# e-paper_ESP32-Pico-D4.net
KiCad netlist of a schematic drawn in EasyEDA Pro
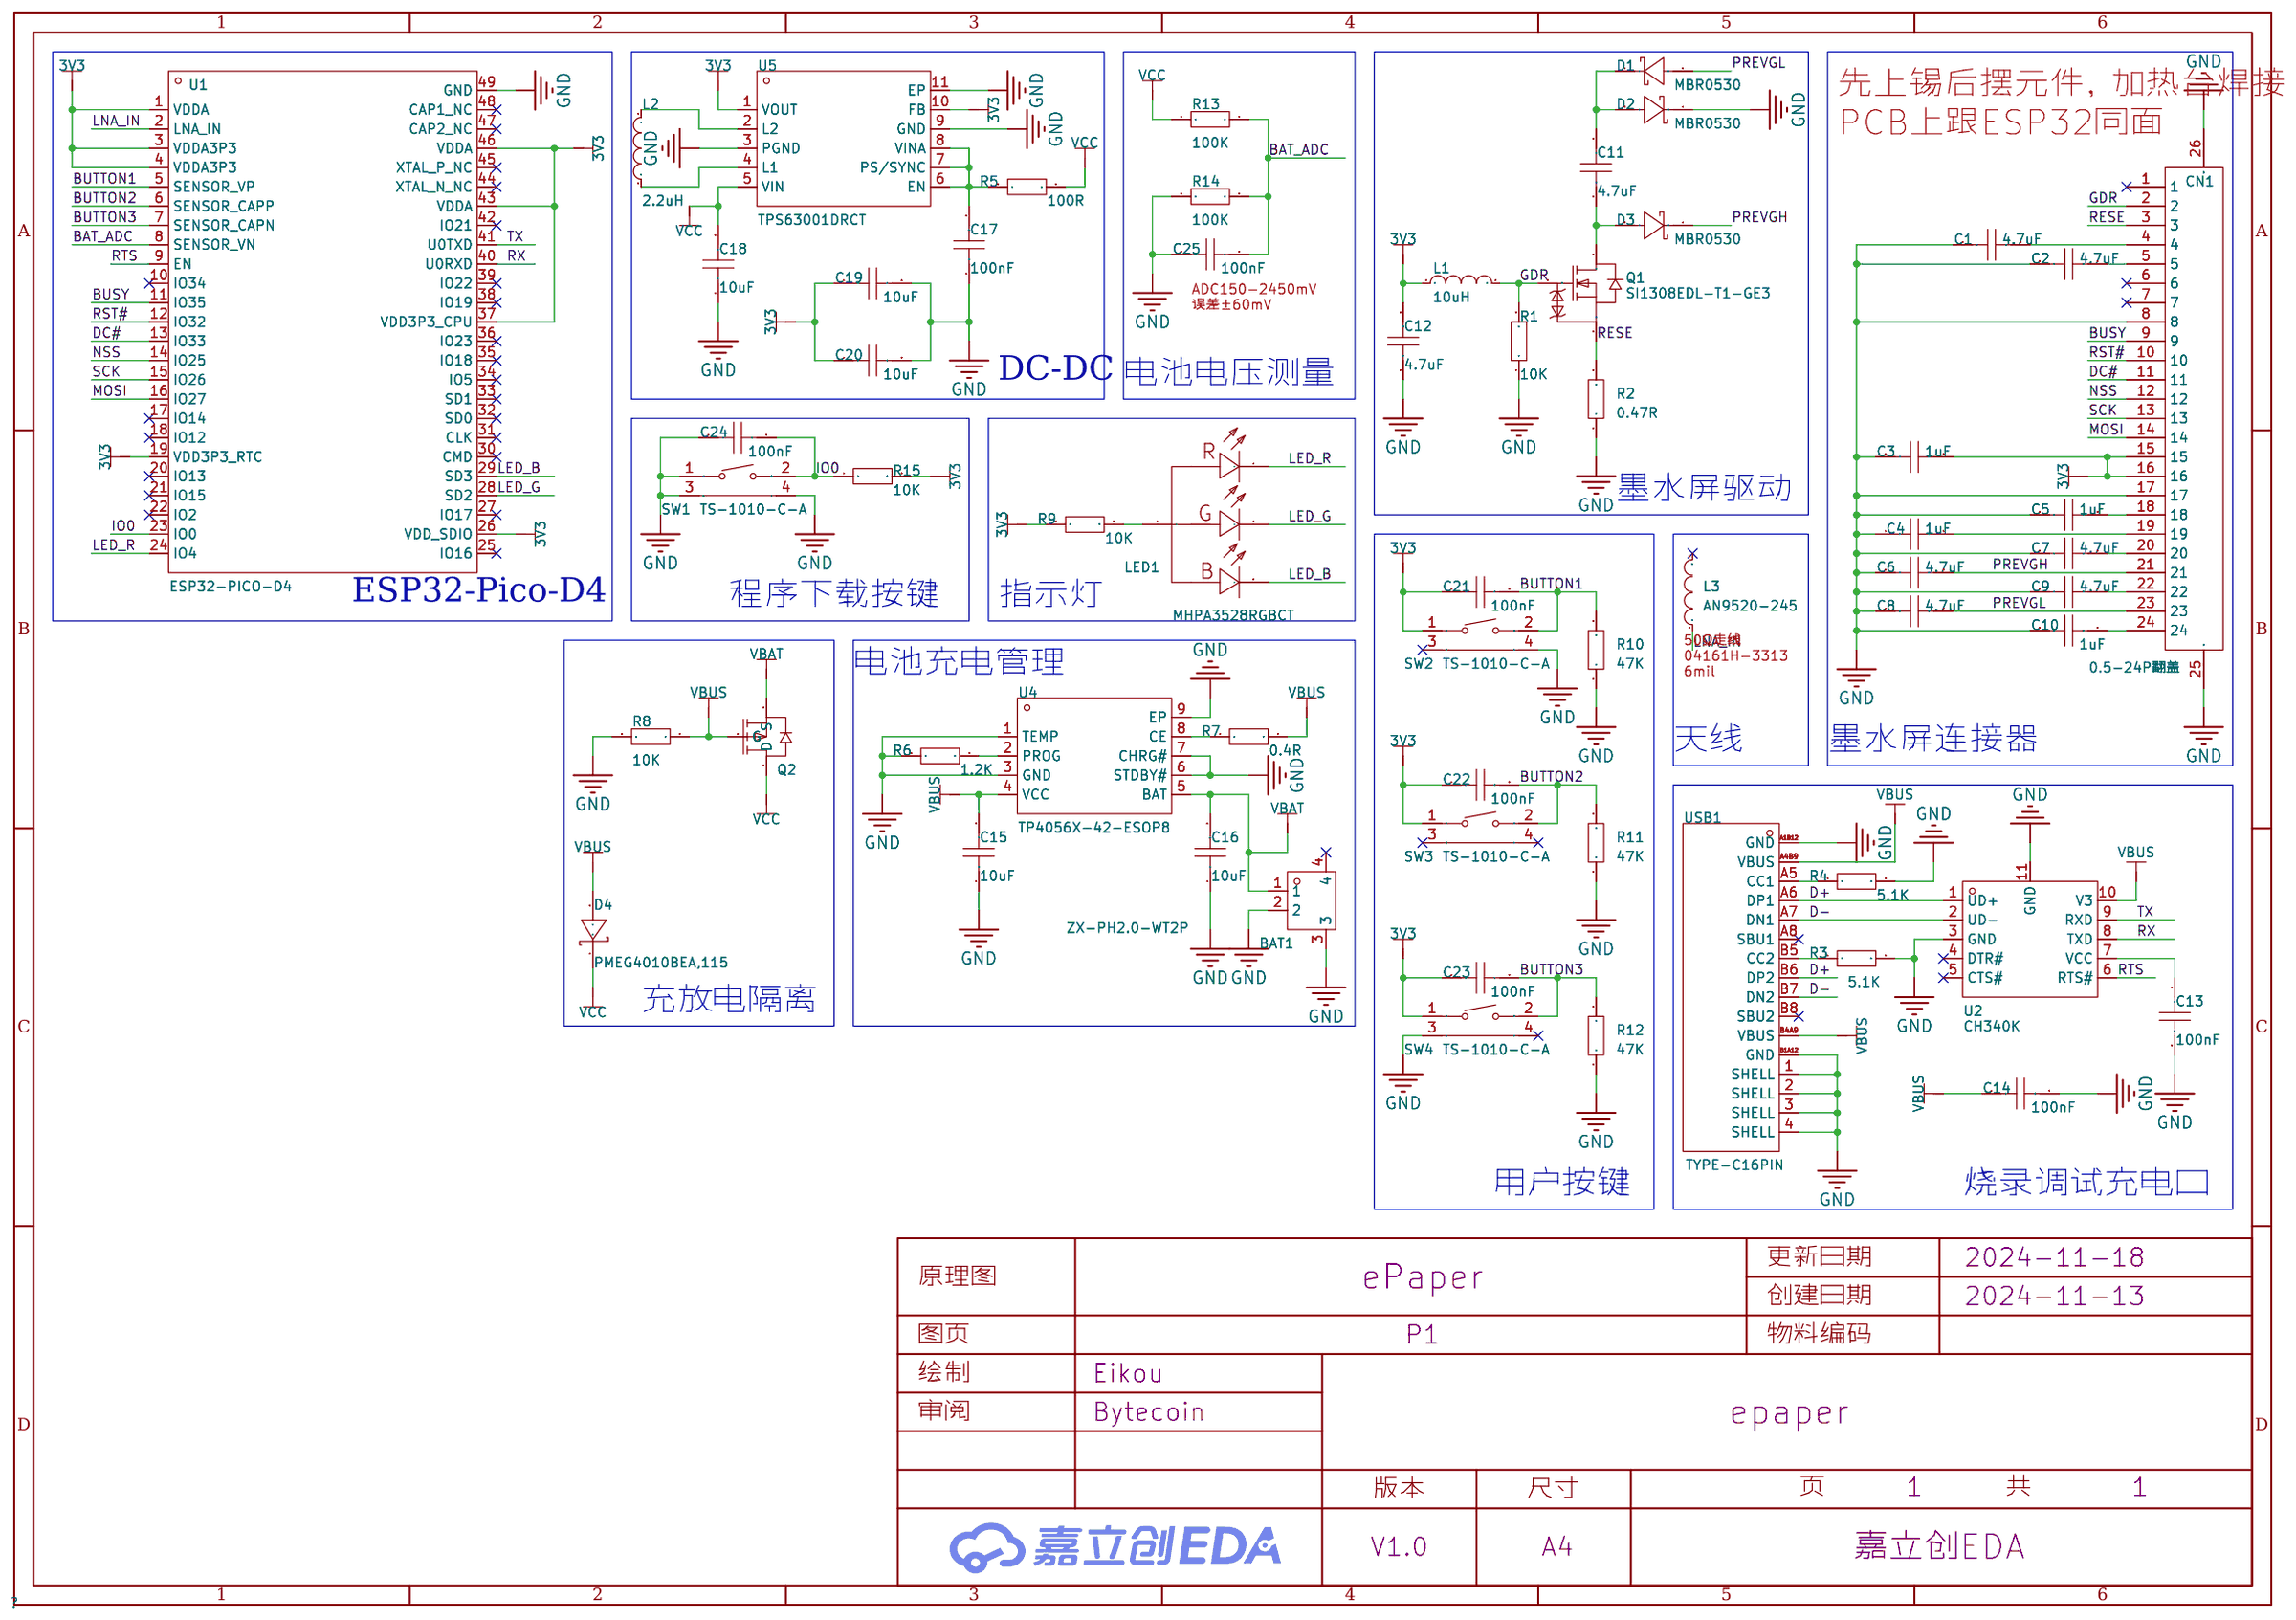
[diagram p0: schematic sheet]

(export (version "E")
  (design (tool "Eeschema 10.0.6"))
  (components
    (comp (ref "BAT1")
      (value "ZX-PH2.0-WT2P")
      (footprint "easyedapro:CONN-SMD_ZX-PH2.0-WT2P")
      (fields (field (name "Manufacturer") "Megastar(兆星)"))
      (libsource (lib "easyedapro") (part "ZX-PH2.0-WT2P"))
    )
    (comp (ref "C1")
      (value "4.7uF")
      (footprint "easyedapro:C0603")
      (libsource (lib "easyedapro") (part "CapAcitance"))
    )
    (comp (ref "C2")
      (value "4.7uF")
      (footprint "easyedapro:C0603")
      (libsource (lib "easyedapro") (part "CapAcitance"))
    )
    (comp (ref "C3")
      (value "1uF")
      (footprint "easyedapro:C0603")
      (libsource (lib "easyedapro") (part "CapAcitance"))
    )
    (comp (ref "C4")
      (value "1uF")
      (footprint "easyedapro:C0603")
      (libsource (lib "easyedapro") (part "CapAcitance"))
    )
    (comp (ref "C5")
      (value "1uF")
      (footprint "easyedapro:C0603")
      (libsource (lib "easyedapro") (part "CapAcitance"))
    )
    (comp (ref "C6")
      (value "4.7uF")
      (footprint "easyedapro:C0603")
      (libsource (lib "easyedapro") (part "CapAcitance"))
    )
    (comp (ref "C7")
      (value "4.7uF")
      (footprint "easyedapro:C0603")
      (libsource (lib "easyedapro") (part "CapAcitance"))
    )
    (comp (ref "C8")
      (value "4.7uF")
      (footprint "easyedapro:C0603")
      (libsource (lib "easyedapro") (part "CapAcitance"))
    )
    (comp (ref "C9")
      (value "4.7uF")
      (footprint "easyedapro:C0603")
      (libsource (lib "easyedapro") (part "CapAcitance"))
    )
    (comp (ref "C10")
      (value "1uF")
      (footprint "easyedapro:C0603")
      (libsource (lib "easyedapro") (part "CapAcitance"))
    )
    (comp (ref "C11")
      (value "4.7uF")
      (footprint "easyedapro:C0603")
      (libsource (lib "easyedapro") (part "CapAcitance"))
    )
    (comp (ref "C12")
      (value "4.7uF")
      (footprint "easyedapro:C0603")
      (libsource (lib "easyedapro") (part "CapAcitance"))
    )
    (comp (ref "C13")
      (value "100nF")
      (footprint "easyedapro:C0603")
      (libsource (lib "easyedapro") (part "CapAcitance"))
    )
    (comp (ref "C14")
      (value "100nF")
      (footprint "easyedapro:C0603")
      (libsource (lib "easyedapro") (part "CapAcitance"))
    )
    (comp (ref "C15")
      (value "10uF")
      (footprint "easyedapro:C0603")
      (libsource (lib "easyedapro") (part "CapAcitance"))
    )
    (comp (ref "C16")
      (value "10uF")
      (footprint "easyedapro:C0603")
      (libsource (lib "easyedapro") (part "CapAcitance"))
    )
    (comp (ref "C17")
      (value "100nF")
      (footprint "easyedapro:C0603")
      (libsource (lib "easyedapro") (part "CapAcitance"))
    )
    (comp (ref "C18")
      (value "10uF")
      (footprint "easyedapro:C0603")
      (libsource (lib "easyedapro") (part "CapAcitance"))
    )
    (comp (ref "C19")
      (value "10uF")
      (footprint "easyedapro:C0603")
      (libsource (lib "easyedapro") (part "CapAcitance"))
    )
    (comp (ref "C20")
      (value "10uF")
      (footprint "easyedapro:C0603")
      (libsource (lib "easyedapro") (part "CapAcitance"))
    )
    (comp (ref "C21")
      (value "100nF")
      (footprint "easyedapro:C0603")
      (libsource (lib "easyedapro") (part "CapAcitance"))
    )
    (comp (ref "C22")
      (value "100nF")
      (footprint "easyedapro:C0603")
      (libsource (lib "easyedapro") (part "CapAcitance"))
    )
    (comp (ref "C23")
      (value "100nF")
      (footprint "easyedapro:C0603")
      (libsource (lib "easyedapro") (part "CapAcitance"))
    )
    (comp (ref "C24")
      (value "100nF")
      (footprint "easyedapro:C0603")
      (libsource (lib "easyedapro") (part "CapAcitance"))
    )
    (comp (ref "C25")
      (value "100nF")
      (footprint "easyedapro:C0603")
      (libsource (lib "easyedapro") (part "CapAcitance"))
    )
    (comp (ref "CN1")
      (value "0.5-24P翻盖")
      (footprint "easyedapro:FPC-SMD_24P-P0.50-L6.1-W16.4")
      (description "间距:0.5mm;触点数量:24P;锁定特性:翻盖式;触点类型:下接;安装类型:卧贴;工作温度范围:-;")
      (fields (field (name "Manufacturer") "BOOMELE(博穆精密)"))
      (libsource (lib "easyedapro") (part "FPC-Pitch0.5-24P-Bottom-Contact-Flip-Lock"))
    )
    (comp (ref "D1")
      (value "MBR0530")
      (footprint "easyedapro:SOD-123_L2.7-W1.6-LS3.7-RD-1")
      (description "二极管配置:独立式;正向压降(Vf):500mV@500mA;直流反向耐压(Vr):30V;整流电流:500mA;")
      (fields (field (name "Manufacturer") "TWGMC(台湾迪嘉)"))
      (libsource (lib "easyedapro") (part "MBR0530_C5204746"))
    )
    (comp (ref "D2")
      (value "MBR0530")
      (footprint "easyedapro:SOD-123_L2.7-W1.6-LS3.7-RD-1")
      (description "二极管配置:独立式;正向压降(Vf):500mV@500mA;直流反向耐压(Vr):30V;整流电流:500mA;")
      (fields (field (name "Manufacturer") "TWGMC(台湾迪嘉)"))
      (libsource (lib "easyedapro") (part "MBR0530_C5204746"))
    )
    (comp (ref "D3")
      (value "MBR0530")
      (footprint "easyedapro:SOD-123_L2.7-W1.6-LS3.7-RD-1")
      (description "二极管配置:独立式;正向压降(Vf):500mV@500mA;直流反向耐压(Vr):30V;整流电流:500mA;")
      (fields (field (name "Manufacturer") "TWGMC(台湾迪嘉)"))
      (libsource (lib "easyedapro") (part "MBR0530_C5204746"))
    )
    (comp (ref "D4")
      (value "PMEG4010BEA,115")
      (fields (field (name "Manufacturer") "Nexperia(安世)"))
      (libsource (lib "easyedapro") (part "SS16"))
    )
    (comp (ref "L1")
      (value "10uH")
      (footprint "easyedapro:IND-SMD_L4.6-W4.1")
      (description "电感值:6.8uH;精度:±20%;额定电流:2A;饱和电流(Isat):2.5A;类型:一体成型电感;")
      (fields (field (name "Manufacturer Part") "CKST0402-10uH/M") (field (name "Manufacturer") "CENKER(岑科)"))
      (libsource (lib "easyedapro") (part "CKST0402-6.8UH/M"))
    )
    (comp (ref "L2")
      (value "2.2uH")
      (footprint "easyedapro:IND-SMD_L4.6-W4.1")
      (description "电感值:6.8uH;精度:±20%;额定电流:2A;饱和电流(Isat):2.5A;类型:一体成型电感;")
      (fields
        (field (name "Manufacturer Part") "CKST0402-2.2uH/M")
        (field (name "Manufacturer") "CENKER(岑科)")
      )
      (libsource (lib "easyedapro") (part "CKST0402-6.8UH/M"))
    )
    (comp (ref "L3")
      (value "AN9520-245")
      (footprint "easyedapro:ANT-SMD_L9.5-W2.1")
      (description "2.4G陶瓷天线/适用于WIFI蓝牙")
      (fields (field (name "Manufacturer") "rainsun(霖昱微)"))
      (libsource (lib "easyedapro") (part "AN9520-245"))
    )
    (comp (ref "LED1")
      (value "MHPA3528RGBCT")
      (footprint "easyedapro:LED-ARRAY-SMD_4P-L3.5-W2.8-TL")
      (fields (field (name "Manufacturer") "MEIHUA(美华)"))
      (libsource (lib "easyedapro") (part "MHPA3528RGBCT"))
    )
    (comp (ref "Q1")
      (value "SI1308EDL-T1-GE3")
      (footprint "easyedapro:SOT-323_L2.0-W1.3-P1.30-LS2.1-BR")
      (description "类型:N沟道;漏源电压(Vdss):30V;连续漏极电流(Id):1.4A;功率(Pd):400mW；500mW;导通电阻(RDS(on)@Vgs,Id):132mΩ@10V,1.4A;")
      (fields (field (name "Manufacturer") "VISHAY(威世)"))
      (libsource (lib "easyedapro") (part "SI1308EDL-T1-GE3"))
    )
    (comp (ref "Q2")
      (value "~")
      (footprint "easyedapro:AO3401A_SOT-23-3")
      (libsource (lib "easyedapro") (part "P_MOS"))
    )
    (comp (ref "R1") (value "10K") (footprint "easyedapro:R0603") (libsource (lib "easyedapro") (part "电阻")))
    (comp (ref "R2")
      (value "0.47R")
      (footprint "easyedapro:R0603")
      (libsource (lib "easyedapro") (part "电阻"))
    )
    (comp (ref "R3") (value "5.1K") (footprint "easyedapro:R0603") (libsource (lib "easyedapro") (part "电阻")))
    (comp (ref "R4") (value "5.1K") (footprint "easyedapro:R0603") (libsource (lib "easyedapro") (part "电阻")))
    (comp (ref "R5") (value "100R") (footprint "easyedapro:R0603") (libsource (lib "easyedapro") (part "电阻")))
    (comp (ref "R6") (value "1.2K") (footprint "easyedapro:R0603") (libsource (lib "easyedapro") (part "电阻")))
    (comp (ref "R7") (value "0.4R") (footprint "easyedapro:R0603") (libsource (lib "easyedapro") (part "电阻")))
    (comp (ref "R8") (value "10K") (footprint "easyedapro:R0603") (libsource (lib "easyedapro") (part "电阻")))
    (comp (ref "R9") (value "10K") (footprint "easyedapro:R0603") (libsource (lib "easyedapro") (part "电阻")))
    (comp (ref "R10") (value "47K") (footprint "easyedapro:R0603") (libsource (lib "easyedapro") (part "电阻")))
    (comp (ref "R11") (value "47K") (footprint "easyedapro:R0603") (libsource (lib "easyedapro") (part "电阻")))
    (comp (ref "R12") (value "47K") (footprint "easyedapro:R0603") (libsource (lib "easyedapro") (part "电阻")))
    (comp (ref "R13")
      (value "100K")
      (footprint "easyedapro:R0603")
      (libsource (lib "easyedapro") (part "电阻"))
    )
    (comp (ref "R14")
      (value "100K")
      (footprint "easyedapro:R0603")
      (libsource (lib "easyedapro") (part "电阻"))
    )
    (comp (ref "R15") (value "10K") (footprint "easyedapro:R0603") (libsource (lib "easyedapro") (part "电阻")))
    (comp (ref "SW1")
      (value "TS-1010-C-A")
      (footprint "easyedapro:KEY-SMD_TX-1010-X-X")
      (fields (field (name "Manufacturer") "XKB Connectivity(中国星坤)"))
      (libsource (lib "easyedapro") (part "TS-1010-C-A"))
    )
    (comp (ref "SW2")
      (value "TS-1010-C-A")
      (footprint "easyedapro:KEY-SMD_TX-1010-X-X")
      (fields (field (name "Manufacturer") "XKB Connectivity(中国星坤)"))
      (libsource (lib "easyedapro") (part "TS-1010-C-A"))
    )
    (comp (ref "SW3")
      (value "TS-1010-C-A")
      (footprint "easyedapro:KEY-SMD_TX-1010-X-X")
      (fields (field (name "Manufacturer") "XKB Connectivity(中国星坤)"))
      (libsource (lib "easyedapro") (part "TS-1010-C-A"))
    )
    (comp (ref "SW4")
      (value "TS-1010-C-A")
      (footprint "easyedapro:KEY-SMD_TX-1010-X-X")
      (fields (field (name "Manufacturer") "XKB Connectivity(中国星坤)"))
      (libsource (lib "easyedapro") (part "TS-1010-C-A"))
    )
    (comp (ref "U1")
      (value "ESP32-PICO-D4")
      (footprint "easyedapro:LGA-48_L7.0-W7.0-P0.50-BL-EP5.4")
      (fields (field (name "Manufacturer") "ESPRESSIF(乐鑫)"))
      (libsource (lib "easyedapro") (part "ESP32-PICO-D4"))
    )
    (comp (ref "U2")
      (value "CH340K")
      (footprint "easyedapro:ESOP-10_L4.9-W3.9-P1.00-LS6.0-BL-EP")
      (description "应用功能:USB转串口;接口协议:USB 2.0;通道数:1;数据速率:2Mbps;")
      (fields (field (name "Manufacturer") "WCH(南京沁恒)"))
      (libsource (lib "easyedapro") (part "CH340K_C18208922"))
    )
    (comp (ref "U4")
      (value "TP4056X-42-ESOP8")
      (footprint "easyedapro:SOP-8_L4.9-W3.9-P1.27-LS6.0-TL-EP")
      (fields (field (name "Manufacturer") "TOPPOWER(南京拓微)"))
      (libsource (lib "easyedapro") (part "TP4056X_C2763448"))
    )
    (comp (ref "U5")
      (value "TPS63001DRCT")
      (footprint "easyedapro:VSON-10_L3.0-W3.0-P0.50-TL-EP")
      (description "功能类型:升降压型;输出类型:固定;输入电压:1.8V~5.5V;输出电压:3.3V;输出电流:1.6A;")
      (fields (field (name "Manufacturer") "TI(德州仪器)"))
      (libsource (lib "easyedapro") (part "TPS63001DRCT"))
    )
    (comp (ref "USB1")
      (value "TYPE-C16PIN")
      (footprint "easyedapro:USB-C-SMD_TYPE-C16PIN")
      (description "连接器类型:Type-C;标准:-;公母:母座;触点数量:16;端口数量:1;安装方式:卧贴;额定电流 - 电源:3A;工作温度范围:-40~+85;")
      (fields (field (name "Manufacturer") "SHOU HAN(首韩)"))
      (libsource (lib "easyedapro") (part "TYPE-C16PIN"))
    )
  )
  (nets
    (net (code "1") (name "/BAT_ADC") (class "Default")
      (node (ref "C25") (pin "2") (pinfunction "2_2") (pintype "input"))
      (node (ref "R13") (pin "1") (pinfunction "1_1") (pintype "input"))
      (node (ref "R14") (pin "1") (pinfunction "1_1") (pintype "input"))
      (node (ref "U1") (pin "8") (pinfunction "SENSOR_VN_8") (pintype "unspecified"))
    )
    (net (code "2") (name "/BUSY") (class "Default")
      (node (ref "CN1") (pin "9") (pinfunction "9_9") (pintype "unspecified"))
      (node (ref "U1") (pin "11") (pinfunction "IO35_11") (pintype "unspecified"))
    )
    (net (code "3") (name "/BUTTON1") (class "Default")
      (node (ref "C21") (pin "2") (pinfunction "2_2") (pintype "input"))
      (node (ref "R10") (pin "2") (pinfunction "2_2") (pintype "input"))
      (node (ref "SW2") (pin "2") (pinfunction "2_2") (pintype "unspecified"))
      (node (ref "U1") (pin "5") (pinfunction "SENSOR_VP_5") (pintype "unspecified"))
    )
    (net (code "4") (name "/BUTTON2") (class "Default")
      (node (ref "C22") (pin "2") (pinfunction "2_2") (pintype "input"))
      (node (ref "R11") (pin "2") (pinfunction "2_2") (pintype "input"))
      (node (ref "SW3") (pin "2") (pinfunction "2_2") (pintype "unspecified"))
      (node (ref "U1") (pin "6") (pinfunction "SENSOR_CAPP_6") (pintype "unspecified"))
    )
    (net (code "5") (name "/BUTTON3") (class "Default")
      (node (ref "C23") (pin "2") (pinfunction "2_2") (pintype "input"))
      (node (ref "R12") (pin "2") (pinfunction "2_2") (pintype "input"))
      (node (ref "SW4") (pin "2") (pinfunction "2_2") (pintype "unspecified"))
      (node (ref "U1") (pin "7") (pinfunction "SENSOR_CAPN_7") (pintype "unspecified"))
    )
    (net (code "6") (name "/D+") (class "Default")
      (node (ref "U2") (pin "1") (pinfunction "UD+_1") (pintype "unspecified"))
      (node (ref "USB1") (pin "A6") (pinfunction "DP1_A6") (pintype "input"))
      (node (ref "USB1") (pin "B6") (pinfunction "DP2_B6") (pintype "input"))
    )
    (net (code "7") (name "/D-") (class "Default")
      (node (ref "U2") (pin "2") (pinfunction "UD-_2") (pintype "unspecified"))
      (node (ref "USB1") (pin "A7") (pinfunction "DN1_A7") (pintype "input"))
      (node (ref "USB1") (pin "B7") (pinfunction "DN2_B7") (pintype "input"))
    )
    (net (code "8") (name "/DC#") (class "Default")
      (node (ref "CN1") (pin "11") (pinfunction "11_11") (pintype "unspecified"))
      (node (ref "U1") (pin "13") (pinfunction "IO33_13") (pintype "unspecified"))
    )
    (net (code "9") (name "/GDR") (class "Default")
      (node (ref "CN1") (pin "2") (pinfunction "2_2") (pintype "unspecified"))
      (node (ref "L1") (pin "2") (pinfunction "2_2") (pintype "unspecified"))
      (node (ref "Q1") (pin "1") (pinfunction "G_1") (pintype "input"))
      (node (ref "R1") (pin "2") (pinfunction "2_2") (pintype "input"))
    )
    (net (code "10") (name "/IO0") (class "Default")
      (node (ref "C24") (pin "2") (pinfunction "2_2") (pintype "input"))
      (node (ref "R15") (pin "1") (pinfunction "1_1") (pintype "input"))
      (node (ref "SW1") (pin "2") (pinfunction "2_2") (pintype "unspecified"))
      (node (ref "U1") (pin "23") (pinfunction "IO0_23") (pintype "unspecified"))
    )
    (net (code "11") (name "/LED_B") (class "Default")
      (node (ref "LED1") (pin "2") (pinfunction "-_2") (pintype "unspecified"))
      (node (ref "U1") (pin "29") (pinfunction "SD3_29") (pintype "unspecified"))
    )
    (net (code "12") (name "/LED_G") (class "Default")
      (node (ref "LED1") (pin "3") (pinfunction "-_3") (pintype "unspecified"))
      (node (ref "U1") (pin "28") (pinfunction "SD2_28") (pintype "unspecified"))
    )
    (net (code "13") (name "/LED_R") (class "Default")
      (node (ref "LED1") (pin "4") (pinfunction "-_4") (pintype "unspecified"))
      (node (ref "U1") (pin "24") (pinfunction "IO4_24") (pintype "unspecified"))
    )
    (net (code "14") (name "/LNA_IN") (class "Default")
      (node (ref "L3") (pin "1") (pinfunction "1_1") (pintype "unspecified"))
      (node (ref "U1") (pin "2") (pinfunction "LNA_IN_2") (pintype "unspecified"))
    )
    (net (code "15") (name "/MOSI") (class "Default")
      (node (ref "CN1") (pin "14") (pinfunction "14_14") (pintype "unspecified"))
      (node (ref "U1") (pin "16") (pinfunction "IO27_16") (pintype "unspecified"))
    )
    (net (code "16") (name "/NSS") (class "Default")
      (node (ref "CN1") (pin "12") (pinfunction "12_12") (pintype "unspecified"))
      (node (ref "U1") (pin "14") (pinfunction "IO25_14") (pintype "unspecified"))
    )
    (net (code "17") (name "/PREVGH") (class "Default")
      (node (ref "C6") (pin "2") (pinfunction "2_2") (pintype "input"))
      (node (ref "CN1") (pin "21") (pinfunction "21_21") (pintype "unspecified"))
      (node (ref "D3") (pin "1") (pinfunction "K_1") (pintype "unspecified"))
    )
    (net (code "18") (name "/PREVGL") (class "Default")
      (node (ref "C8") (pin "2") (pinfunction "2_2") (pintype "input"))
      (node (ref "CN1") (pin "23") (pinfunction "23_23") (pintype "unspecified"))
      (node (ref "D1") (pin "2") (pinfunction "A_2") (pintype "unspecified"))
    )
    (net (code "19") (name "/RESE") (class "Default")
      (node (ref "CN1") (pin "3") (pinfunction "3_3") (pintype "unspecified"))
      (node (ref "Q1") (pin "2") (pinfunction "S_2") (pintype "input"))
      (node (ref "R2") (pin "2") (pinfunction "2_2") (pintype "input"))
    )
    (net (code "20") (name "/RST#") (class "Default")
      (node (ref "CN1") (pin "10") (pinfunction "10_10") (pintype "unspecified"))
      (node (ref "U1") (pin "12") (pinfunction "IO32_12") (pintype "unspecified"))
    )
    (net (code "21") (name "/RTS") (class "Default")
      (node (ref "U1") (pin "9") (pinfunction "EN_9") (pintype "unspecified"))
      (node (ref "U2") (pin "6") (pinfunction "RTS#_6") (pintype "unspecified"))
    )
    (net (code "22") (name "/RX") (class "Default")
      (node (ref "U1") (pin "40") (pinfunction "U0RXD_40") (pintype "unspecified"))
      (node (ref "U2") (pin "8") (pinfunction "TXD_8") (pintype "unspecified"))
    )
    (net (code "23") (name "/SCK") (class "Default")
      (node (ref "CN1") (pin "13") (pinfunction "13_13") (pintype "unspecified"))
      (node (ref "U1") (pin "15") (pinfunction "IO26_15") (pintype "unspecified"))
    )
    (net (code "24") (name "/TX") (class "Default")
      (node (ref "U1") (pin "41") (pinfunction "U0TXD_41") (pintype "unspecified"))
      (node (ref "U2") (pin "9") (pinfunction "RXD_9") (pintype "unspecified"))
    )
    (net (code "25") (name "3V3") (class "Default")
      (node (ref "C12") (pin "2") (pinfunction "2_2") (pintype "input"))
      (node (ref "C19") (pin "1") (pinfunction "1_1") (pintype "input"))
      (node (ref "C20") (pin "1") (pinfunction "1_1") (pintype "input"))
      (node (ref "C21") (pin "1") (pinfunction "1_1") (pintype "input"))
      (node (ref "C22") (pin "1") (pinfunction "1_1") (pintype "input"))
      (node (ref "C23") (pin "1") (pinfunction "1_1") (pintype "input"))
      (node (ref "C3") (pin "2") (pinfunction "2_2") (pintype "input"))
      (node (ref "CN1") (pin "15") (pinfunction "15_15") (pintype "unspecified"))
      (node (ref "CN1") (pin "16") (pinfunction "16_16") (pintype "unspecified"))
      (node (ref "L1") (pin "1") (pinfunction "1_1") (pintype "unspecified"))
      (node (ref "R15") (pin "2") (pinfunction "2_2") (pintype "input"))
      (node (ref "R9") (pin "1") (pinfunction "1_1") (pintype "input"))
      (node (ref "SW2") (pin "1") (pinfunction "1_1") (pintype "unspecified"))
      (node (ref "SW3") (pin "1") (pinfunction "1_1") (pintype "unspecified"))
      (node (ref "SW4") (pin "1") (pinfunction "1_1") (pintype "unspecified"))
      (node (ref "U1") (pin "1") (pinfunction "VDDA_1") (pintype "unspecified"))
      (node (ref "U1") (pin "19") (pinfunction "VDD3P3_RTC_19") (pintype "unspecified"))
      (node (ref "U1") (pin "26") (pinfunction "VDD_SDIO_26") (pintype "unspecified"))
      (node (ref "U1") (pin "3") (pinfunction "VDDA3P3_3") (pintype "unspecified"))
      (node (ref "U1") (pin "37") (pinfunction "VDD3P3_CPU_37") (pintype "unspecified"))
      (node (ref "U1") (pin "4") (pinfunction "VDDA3P3_4") (pintype "unspecified"))
      (node (ref "U1") (pin "43") (pinfunction "VDDA_43") (pintype "unspecified"))
      (node (ref "U1") (pin "46") (pinfunction "VDDA_46") (pintype "unspecified"))
      (node (ref "U5") (pin "1") (pinfunction "VOUT_1") (pintype "unspecified"))
      (node (ref "U5") (pin "10") (pinfunction "FB_10") (pintype "unspecified"))
    )
    (net (code "26") (name "GND") (class "Default")
      (node (ref "BAT1") (pin "2") (pinfunction "2_2") (pintype "unspecified"))
      (node (ref "BAT1") (pin "3") (pinfunction "3_3") (pintype "unspecified"))
      (node (ref "C1") (pin "1") (pinfunction "1_1") (pintype "input"))
      (node (ref "C10") (pin "1") (pinfunction "1_1") (pintype "input"))
      (node (ref "C12") (pin "1") (pinfunction "1_1") (pintype "input"))
      (node (ref "C13") (pin "2") (pinfunction "2_2") (pintype "input"))
      (node (ref "C14") (pin "2") (pinfunction "2_2") (pintype "input"))
      (node (ref "C15") (pin "1") (pinfunction "1_1") (pintype "input"))
      (node (ref "C16") (pin "1") (pinfunction "1_1") (pintype "input"))
      (node (ref "C17") (pin "1") (pinfunction "1_1") (pintype "input"))
      (node (ref "C18") (pin "1") (pinfunction "1_1") (pintype "input"))
      (node (ref "C19") (pin "2") (pinfunction "2_2") (pintype "input"))
      (node (ref "C2") (pin "1") (pinfunction "1_1") (pintype "input"))
      (node (ref "C20") (pin "2") (pinfunction "2_2") (pintype "input"))
      (node (ref "C24") (pin "1") (pinfunction "1_1") (pintype "input"))
      (node (ref "C25") (pin "1") (pinfunction "1_1") (pintype "input"))
      (node (ref "C3") (pin "1") (pinfunction "1_1") (pintype "input"))
      (node (ref "C4") (pin "1") (pinfunction "1_1") (pintype "input"))
      (node (ref "C5") (pin "1") (pinfunction "1_1") (pintype "input"))
      (node (ref "C6") (pin "1") (pinfunction "1_1") (pintype "input"))
      (node (ref "C7") (pin "1") (pinfunction "1_1") (pintype "input"))
      (node (ref "C8") (pin "1") (pinfunction "1_1") (pintype "input"))
      (node (ref "C9") (pin "1") (pinfunction "1_1") (pintype "input"))
      (node (ref "CN1") (pin "17") (pinfunction "17_17") (pintype "unspecified"))
      (node (ref "CN1") (pin "25") (pinfunction "25_25") (pintype "unspecified"))
      (node (ref "CN1") (pin "26") (pinfunction "26_26") (pintype "unspecified"))
      (node (ref "CN1") (pin "8") (pinfunction "8_8") (pintype "unspecified"))
      (node (ref "D2") (pin "1") (pinfunction "K_1") (pintype "unspecified"))
      (node (ref "R1") (pin "1") (pinfunction "1_1") (pintype "input"))
      (node (ref "R10") (pin "1") (pinfunction "1_1") (pintype "input"))
      (node (ref "R11") (pin "1") (pinfunction "1_1") (pintype "input"))
      (node (ref "R12") (pin "1") (pinfunction "1_1") (pintype "input"))
      (node (ref "R14") (pin "2") (pinfunction "2_2") (pintype "input"))
      (node (ref "R2") (pin "1") (pinfunction "1_1") (pintype "input"))
      (node (ref "R3") (pin "2") (pinfunction "2_2") (pintype "input"))
      (node (ref "R4") (pin "2") (pinfunction "2_2") (pintype "input"))
      (node (ref "R6") (pin "1") (pinfunction "1_1") (pintype "input"))
      (node (ref "R8") (pin "2") (pinfunction "2_2") (pintype "input"))
      (node (ref "SW1") (pin "1") (pinfunction "1_1") (pintype "unspecified"))
      (node (ref "SW1") (pin "3") (pinfunction "3_3") (pintype "unspecified"))
      (node (ref "SW1") (pin "4") (pinfunction "4_4") (pintype "unspecified"))
      (node (ref "SW2") (pin "4") (pinfunction "4_4") (pintype "unspecified"))
      (node (ref "SW4") (pin "3") (pinfunction "3_3") (pintype "unspecified"))
      (node (ref "U1") (pin "49") (pinfunction "GND_49") (pintype "unspecified"))
      (node (ref "U2") (pin "11") (pinfunction "GND_11") (pintype "unspecified"))
      (node (ref "U2") (pin "3") (pinfunction "GND_3") (pintype "unspecified"))
      (node (ref "U4") (pin "1") (pinfunction "TEMP_1") (pintype "unspecified"))
      (node (ref "U4") (pin "3") (pinfunction "GND_3") (pintype "unspecified"))
      (node (ref "U4") (pin "6") (pinfunction "STDBY#_6") (pintype "unspecified"))
      (node (ref "U4") (pin "7") (pinfunction "CHRG#_7") (pintype "unspecified"))
      (node (ref "U4") (pin "9") (pinfunction "EP_9") (pintype "unspecified"))
      (node (ref "U5") (pin "11") (pinfunction "EP_11") (pintype "unspecified"))
      (node (ref "U5") (pin "3") (pinfunction "PGND_3") (pintype "unspecified"))
      (node (ref "U5") (pin "9") (pinfunction "GND_9") (pintype "unspecified"))
      (node (ref "USB1") (pin "1") (pinfunction "SHELL_1") (pintype "input"))
      (node (ref "USB1") (pin "2") (pinfunction "SHELL_2") (pintype "input"))
      (node (ref "USB1") (pin "3") (pinfunction "SHELL_3") (pintype "input"))
      (node (ref "USB1") (pin "4") (pinfunction "SHELL_4") (pintype "input"))
      (node (ref "USB1") (pin "A1B12") (pinfunction "GND_A1B12") (pintype "input"))
      (node (ref "USB1") (pin "B1A12") (pinfunction "GND_B1A12") (pintype "input"))
    )
    (net (code "27") (name "Net-(C1-Pad2)") (class "Default")
      (node (ref "C1") (pin "2") (pinfunction "2_2") (pintype "input"))
      (node (ref "CN1") (pin "4") (pinfunction "4_4") (pintype "unspecified"))
    )
    (net (code "28") (name "Net-(C2-Pad2)") (class "Default")
      (node (ref "C2") (pin "2") (pinfunction "2_2") (pintype "input"))
      (node (ref "CN1") (pin "5") (pinfunction "5_5") (pintype "unspecified"))
    )
    (net (code "29") (name "Net-(C4-Pad2)") (class "Default")
      (node (ref "C4") (pin "2") (pinfunction "2_2") (pintype "input"))
      (node (ref "CN1") (pin "19") (pinfunction "19_19") (pintype "unspecified"))
    )
    (net (code "30") (name "Net-(C5-Pad2)") (class "Default")
      (node (ref "C5") (pin "2") (pinfunction "2_2") (pintype "input"))
      (node (ref "CN1") (pin "18") (pinfunction "18_18") (pintype "unspecified"))
    )
    (net (code "31") (name "Net-(C7-Pad2)") (class "Default")
      (node (ref "C7") (pin "2") (pinfunction "2_2") (pintype "input"))
      (node (ref "CN1") (pin "20") (pinfunction "20_20") (pintype "unspecified"))
    )
    (net (code "32") (name "Net-(C9-Pad2)") (class "Default")
      (node (ref "C9") (pin "2") (pinfunction "2_2") (pintype "input"))
      (node (ref "CN1") (pin "22") (pinfunction "22_22") (pintype "unspecified"))
    )
    (net (code "33") (name "Net-(C10-Pad2)") (class "Default")
      (node (ref "C10") (pin "2") (pinfunction "2_2") (pintype "input"))
      (node (ref "CN1") (pin "24") (pinfunction "24_24") (pintype "unspecified"))
    )
    (net (code "34") (name "Net-(D1-K)") (class "Default")
      (node (ref "C11") (pin "2") (pinfunction "2_2") (pintype "input"))
      (node (ref "D1") (pin "1") (pinfunction "K_1") (pintype "unspecified"))
      (node (ref "D2") (pin "2") (pinfunction "A_2") (pintype "unspecified"))
    )
    (net (code "35") (name "Net-(D3-A)") (class "Default")
      (node (ref "C11") (pin "1") (pinfunction "1_1") (pintype "input"))
      (node (ref "D3") (pin "2") (pinfunction "A_2") (pintype "unspecified"))
      (node (ref "Q1") (pin "3") (pinfunction "D_3") (pintype "input"))
    )
    (net (code "36") (name "Net-(LED1---Pad1)") (class "Default")
      (node (ref "LED1") (pin "1") (pinfunction "-_1") (pintype "unspecified"))
      (node (ref "R9") (pin "2") (pinfunction "2_2") (pintype "input"))
    )
    (net (code "37") (name "Net-(U2-VCC)") (class "Default")
      (node (ref "C13") (pin "1") (pinfunction "1_1") (pintype "input"))
      (node (ref "U2") (pin "7") (pinfunction "VCC_7") (pintype "unspecified"))
    )
    (net (code "38") (name "Net-(U4-CE)") (class "Default")
      (node (ref "R7") (pin "1") (pinfunction "1_1") (pintype "input"))
      (node (ref "U4") (pin "8") (pinfunction "CE_8") (pintype "unspecified"))
    )
    (net (code "39") (name "Net-(U4-PROG)") (class "Default")
      (node (ref "R6") (pin "2") (pinfunction "2_2") (pintype "input"))
      (node (ref "U4") (pin "2") (pinfunction "PROG_2") (pintype "unspecified"))
    )
    (net (code "40") (name "Net-(U5-EN)") (class "Default")
      (node (ref "C17") (pin "2") (pinfunction "2_2") (pintype "input"))
      (node (ref "R5") (pin "1") (pinfunction "1_1") (pintype "input"))
      (node (ref "U5") (pin "6") (pinfunction "EN_6") (pintype "unspecified"))
      (node (ref "U5") (pin "7") (pinfunction "PS/SYNC_7") (pintype "unspecified"))
      (node (ref "U5") (pin "8") (pinfunction "VINA_8") (pintype "unspecified"))
    )
    (net (code "41") (name "Net-(U5-L1)") (class "Default")
      (node (ref "L2") (pin "1") (pinfunction "1_1") (pintype "unspecified"))
      (node (ref "U5") (pin "4") (pinfunction "L1_4") (pintype "unspecified"))
    )
    (net (code "42") (name "Net-(U5-L2)") (class "Default")
      (node (ref "L2") (pin "2") (pinfunction "2_2") (pintype "unspecified"))
      (node (ref "U5") (pin "2") (pinfunction "L2_2") (pintype "unspecified"))
    )
    (net (code "43") (name "Net-(USB1-CC1)") (class "Default")
      (node (ref "R4") (pin "1") (pinfunction "1_1") (pintype "input"))
      (node (ref "USB1") (pin "A5") (pinfunction "CC1_A5") (pintype "input"))
    )
    (net (code "44") (name "Net-(USB1-CC2)") (class "Default")
      (node (ref "R3") (pin "1") (pinfunction "1_1") (pintype "input"))
      (node (ref "USB1") (pin "B5") (pinfunction "CC2_B5") (pintype "input"))
    )
    (net (code "45") (name "VBAT") (class "Default")
      (node (ref "BAT1") (pin "1") (pinfunction "1_1") (pintype "unspecified"))
      (node (ref "C16") (pin "2") (pinfunction "2_2") (pintype "input"))
      (node (ref "Q2") (pin "2") (pinfunction "S_2") (pintype "input"))
      (node (ref "U4") (pin "5") (pinfunction "BAT_5") (pintype "unspecified"))
    )
    (net (code "46") (name "VBUS") (class "Default")
      (node (ref "C14") (pin "1") (pinfunction "1_1") (pintype "input"))
      (node (ref "C15") (pin "2") (pinfunction "2_2") (pintype "input"))
      (node (ref "D4") (pin "2") (pinfunction "A_2") (pintype "unspecified"))
      (node (ref "Q2") (pin "1") (pinfunction "G_1") (pintype "input"))
      (node (ref "R7") (pin "2") (pinfunction "2_2") (pintype "input"))
      (node (ref "R8") (pin "1") (pinfunction "1_1") (pintype "input"))
      (node (ref "U2") (pin "10") (pinfunction "V3_10") (pintype "unspecified"))
      (node (ref "U4") (pin "4") (pinfunction "VCC_4") (pintype "unspecified"))
      (node (ref "USB1") (pin "A4B9") (pinfunction "VBUS_A4B9") (pintype "input"))
      (node (ref "USB1") (pin "B4A9") (pinfunction "VBUS_B4A9") (pintype "input"))
    )
    (net (code "47") (name "VCC") (class "Default")
      (node (ref "C18") (pin "2") (pinfunction "2_2") (pintype "input"))
      (node (ref "D4") (pin "1") (pinfunction "K_1") (pintype "unspecified"))
      (node (ref "Q2") (pin "3") (pinfunction "D_3") (pintype "input"))
      (node (ref "R13") (pin "2") (pinfunction "2_2") (pintype "input"))
      (node (ref "R5") (pin "2") (pinfunction "2_2") (pintype "input"))
      (node (ref "U5") (pin "5") (pinfunction "VIN_5") (pintype "unspecified"))
    )
    (net (code "48") (name "unconnected-(BAT1-Pad4)") (class "Default")
      (node (ref "BAT1") (pin "4") (pinfunction "4_4") (pintype "unspecified+no_connect"))
    )
    (net (code "49") (name "unconnected-(CN1-Pad1)") (class "Default")
      (node (ref "CN1") (pin "1") (pinfunction "1_1") (pintype "unspecified+no_connect"))
    )
    (net (code "50") (name "unconnected-(CN1-Pad6)") (class "Default")
      (node (ref "CN1") (pin "6") (pinfunction "6_6") (pintype "unspecified+no_connect"))
    )
    (net (code "51") (name "unconnected-(CN1-Pad7)") (class "Default")
      (node (ref "CN1") (pin "7") (pinfunction "7_7") (pintype "unspecified+no_connect"))
    )
    (net (code "52") (name "unconnected-(L3-Pad2)") (class "Default")
      (node (ref "L3") (pin "2") (pinfunction "2_2") (pintype "unspecified+no_connect"))
    )
    (net (code "53") (name "unconnected-(SW2-Pad3)") (class "Default")
      (node (ref "SW2") (pin "3") (pinfunction "3_3") (pintype "unspecified+no_connect"))
    )
    (net (code "54") (name "unconnected-(SW3-Pad3)") (class "Default")
      (node (ref "SW3") (pin "3") (pinfunction "3_3") (pintype "unspecified+no_connect"))
    )
    (net (code "55") (name "unconnected-(SW3-Pad4)") (class "Default")
      (node (ref "SW3") (pin "4") (pinfunction "4_4") (pintype "unspecified+no_connect"))
    )
    (net (code "56") (name "unconnected-(SW4-Pad4)") (class "Default")
      (node (ref "SW4") (pin "4") (pinfunction "4_4") (pintype "unspecified+no_connect"))
    )
    (net (code "57") (name "unconnected-(U1-CAP1_NC-Pad48)") (class "Default")
      (node (ref "U1") (pin "48") (pinfunction "CAP1_NC_48") (pintype "unspecified+no_connect"))
    )
    (net (code "58") (name "unconnected-(U1-CAP2_NC-Pad47)") (class "Default")
      (node (ref "U1") (pin "47") (pinfunction "CAP2_NC_47") (pintype "unspecified+no_connect"))
    )
    (net (code "59") (name "unconnected-(U1-CLK-Pad31)") (class "Default")
      (node (ref "U1") (pin "31") (pinfunction "CLK_31") (pintype "unspecified+no_connect"))
    )
    (net (code "60") (name "unconnected-(U1-CMD-Pad30)") (class "Default")
      (node (ref "U1") (pin "30") (pinfunction "CMD_30") (pintype "unspecified+no_connect"))
    )
    (net (code "61") (name "unconnected-(U1-IO2-Pad22)") (class "Default")
      (node (ref "U1") (pin "22") (pinfunction "IO2_22") (pintype "unspecified+no_connect"))
    )
    (net (code "62") (name "unconnected-(U1-IO5-Pad34)") (class "Default")
      (node (ref "U1") (pin "34") (pinfunction "IO5_34") (pintype "unspecified+no_connect"))
    )
    (net (code "63") (name "unconnected-(U1-IO12-Pad18)") (class "Default")
      (node (ref "U1") (pin "18") (pinfunction "IO12_18") (pintype "unspecified+no_connect"))
    )
    (net (code "64") (name "unconnected-(U1-IO13-Pad20)") (class "Default")
      (node (ref "U1") (pin "20") (pinfunction "IO13_20") (pintype "unspecified+no_connect"))
    )
    (net (code "65") (name "unconnected-(U1-IO14-Pad17)") (class "Default")
      (node (ref "U1") (pin "17") (pinfunction "IO14_17") (pintype "unspecified+no_connect"))
    )
    (net (code "66") (name "unconnected-(U1-IO15-Pad21)") (class "Default")
      (node (ref "U1") (pin "21") (pinfunction "IO15_21") (pintype "unspecified+no_connect"))
    )
    (net (code "67") (name "unconnected-(U1-IO16-Pad25)") (class "Default")
      (node (ref "U1") (pin "25") (pinfunction "IO16_25") (pintype "unspecified+no_connect"))
    )
    (net (code "68") (name "unconnected-(U1-IO17-Pad27)") (class "Default")
      (node (ref "U1") (pin "27") (pinfunction "IO17_27") (pintype "unspecified+no_connect"))
    )
    (net (code "69") (name "unconnected-(U1-IO18-Pad35)") (class "Default")
      (node (ref "U1") (pin "35") (pinfunction "IO18_35") (pintype "unspecified+no_connect"))
    )
    (net (code "70") (name "unconnected-(U1-IO19-Pad38)") (class "Default")
      (node (ref "U1") (pin "38") (pinfunction "IO19_38") (pintype "unspecified+no_connect"))
    )
    (net (code "71") (name "unconnected-(U1-IO21-Pad42)") (class "Default")
      (node (ref "U1") (pin "42") (pinfunction "IO21_42") (pintype "unspecified+no_connect"))
    )
    (net (code "72") (name "unconnected-(U1-IO22-Pad39)") (class "Default")
      (node (ref "U1") (pin "39") (pinfunction "IO22_39") (pintype "unspecified+no_connect"))
    )
    (net (code "73") (name "unconnected-(U1-IO23-Pad36)") (class "Default")
      (node (ref "U1") (pin "36") (pinfunction "IO23_36") (pintype "unspecified+no_connect"))
    )
    (net (code "74") (name "unconnected-(U1-IO34-Pad10)") (class "Default")
      (node (ref "U1") (pin "10") (pinfunction "IO34_10") (pintype "unspecified+no_connect"))
    )
    (net (code "75") (name "unconnected-(U1-SD0-Pad32)") (class "Default")
      (node (ref "U1") (pin "32") (pinfunction "SD0_32") (pintype "unspecified+no_connect"))
    )
    (net (code "76") (name "unconnected-(U1-SD1-Pad33)") (class "Default")
      (node (ref "U1") (pin "33") (pinfunction "SD1_33") (pintype "unspecified+no_connect"))
    )
    (net (code "77") (name "unconnected-(U1-XTAL_N_NC-Pad44)") (class "Default")
      (node (ref "U1") (pin "44") (pinfunction "XTAL_N_NC_44") (pintype "unspecified+no_connect"))
    )
    (net (code "78") (name "unconnected-(U1-XTAL_P_NC-Pad45)") (class "Default")
      (node (ref "U1") (pin "45") (pinfunction "XTAL_P_NC_45") (pintype "unspecified+no_connect"))
    )
    (net (code "79") (name "unconnected-(U2-CTS#-Pad5)") (class "Default")
      (node (ref "U2") (pin "5") (pinfunction "CTS#_5") (pintype "unspecified+no_connect"))
    )
    (net (code "80") (name "unconnected-(U2-DTR#-Pad4)") (class "Default")
      (node (ref "U2") (pin "4") (pinfunction "DTR#_4") (pintype "unspecified+no_connect"))
    )
    (net (code "81") (name "unconnected-(USB1-SBU1-PadA8)") (class "Default")
      (node (ref "USB1") (pin "A8") (pinfunction "SBU1_A8") (pintype "input+no_connect"))
    )
    (net (code "82") (name "unconnected-(USB1-SBU2-PadB8)") (class "Default")
      (node (ref "USB1") (pin "B8") (pinfunction "SBU2_B8") (pintype "input+no_connect"))
    )
  )
)
